# 24line-control-panel.net
KiCad netlist of a schematic drawn in Altium Designer
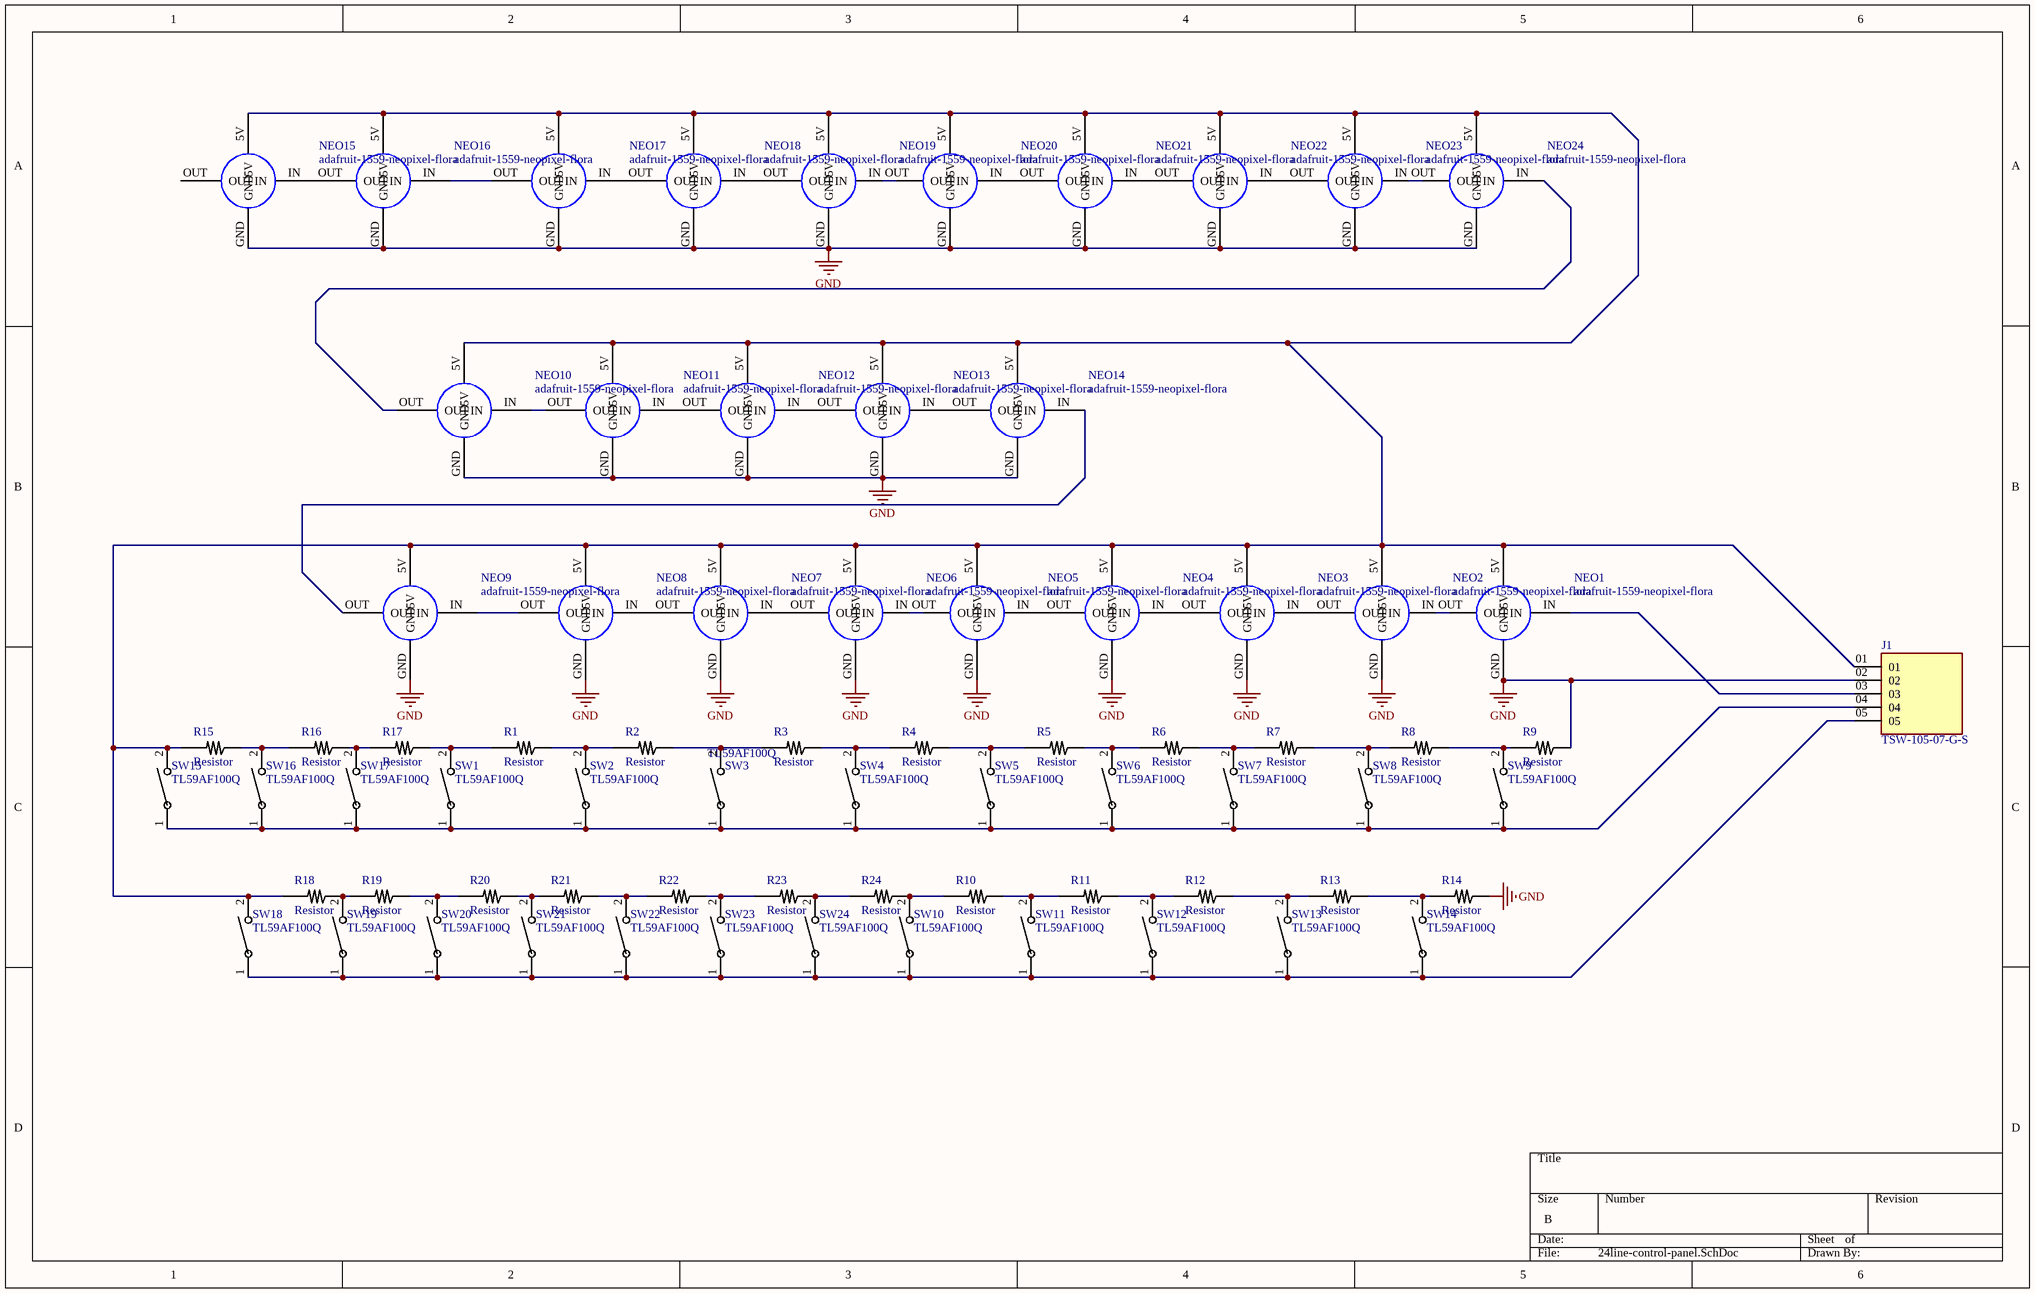
[diagram p0: 24line-control-panel.SchDoc]

(export (version "E")
  (design (tool "Eeschema 10.0.6"))
  (components
    (comp (ref "J1")
      (value "TSW-105-07-G-S")
      (footprint "SAMTEC_TSW-105-07-G-S")
      (fields (field (name "MF") "Samtec Inc."))
      (libsource (lib "SchlibLafe") (part "TSW-105-07-G-S"))
    )
    (comp (ref "NEO1")
      (value "adafruit-1559-neopixel-flora")
      (footprint "adafruit-1559-neopixel-flora")
      (libsource (lib "SchlibLafe") (part "adafruit-1559-neopixel-flora"))
    )
    (comp (ref "NEO2")
      (value "adafruit-1559-neopixel-flora")
      (footprint "adafruit-1559-neopixel-flora")
      (libsource (lib "SchlibLafe") (part "adafruit-1559-neopixel-flora"))
    )
    (comp (ref "NEO3")
      (value "adafruit-1559-neopixel-flora")
      (footprint "adafruit-1559-neopixel-flora")
      (libsource (lib "SchlibLafe") (part "adafruit-1559-neopixel-flora"))
    )
    (comp (ref "NEO4")
      (value "adafruit-1559-neopixel-flora")
      (footprint "adafruit-1559-neopixel-flora")
      (libsource (lib "SchlibLafe") (part "adafruit-1559-neopixel-flora"))
    )
    (comp (ref "NEO5")
      (value "adafruit-1559-neopixel-flora")
      (footprint "adafruit-1559-neopixel-flora")
      (libsource (lib "SchlibLafe") (part "adafruit-1559-neopixel-flora"))
    )
    (comp (ref "NEO6")
      (value "adafruit-1559-neopixel-flora")
      (footprint "adafruit-1559-neopixel-flora")
      (libsource (lib "SchlibLafe") (part "adafruit-1559-neopixel-flora"))
    )
    (comp (ref "NEO7")
      (value "adafruit-1559-neopixel-flora")
      (footprint "adafruit-1559-neopixel-flora")
      (libsource (lib "SchlibLafe") (part "adafruit-1559-neopixel-flora"))
    )
    (comp (ref "NEO8")
      (value "adafruit-1559-neopixel-flora")
      (footprint "adafruit-1559-neopixel-flora")
      (libsource (lib "SchlibLafe") (part "adafruit-1559-neopixel-flora"))
    )
    (comp (ref "NEO9")
      (value "adafruit-1559-neopixel-flora")
      (footprint "adafruit-1559-neopixel-flora")
      (libsource (lib "SchlibLafe") (part "adafruit-1559-neopixel-flora"))
    )
    (comp (ref "NEO10")
      (value "adafruit-1559-neopixel-flora")
      (footprint "adafruit-1559-neopixel-flora")
      (libsource (lib "SchlibLafe") (part "adafruit-1559-neopixel-flora"))
    )
    (comp (ref "NEO11")
      (value "adafruit-1559-neopixel-flora")
      (footprint "adafruit-1559-neopixel-flora")
      (libsource (lib "SchlibLafe") (part "adafruit-1559-neopixel-flora"))
    )
    (comp (ref "NEO12")
      (value "adafruit-1559-neopixel-flora")
      (footprint "adafruit-1559-neopixel-flora")
      (libsource (lib "SchlibLafe") (part "adafruit-1559-neopixel-flora"))
    )
    (comp (ref "NEO13")
      (value "adafruit-1559-neopixel-flora")
      (footprint "adafruit-1559-neopixel-flora")
      (libsource (lib "SchlibLafe") (part "adafruit-1559-neopixel-flora"))
    )
    (comp (ref "NEO14")
      (value "adafruit-1559-neopixel-flora")
      (footprint "adafruit-1559-neopixel-flora")
      (libsource (lib "SchlibLafe") (part "adafruit-1559-neopixel-flora"))
    )
    (comp (ref "NEO15")
      (value "adafruit-1559-neopixel-flora")
      (footprint "adafruit-1559-neopixel-flora")
      (libsource (lib "SchlibLafe") (part "adafruit-1559-neopixel-flora"))
    )
    (comp (ref "NEO16")
      (value "adafruit-1559-neopixel-flora")
      (footprint "adafruit-1559-neopixel-flora")
      (libsource (lib "SchlibLafe") (part "adafruit-1559-neopixel-flora"))
    )
    (comp (ref "NEO17")
      (value "adafruit-1559-neopixel-flora")
      (footprint "adafruit-1559-neopixel-flora")
      (libsource (lib "SchlibLafe") (part "adafruit-1559-neopixel-flora"))
    )
    (comp (ref "NEO18")
      (value "adafruit-1559-neopixel-flora")
      (footprint "adafruit-1559-neopixel-flora")
      (libsource (lib "SchlibLafe") (part "adafruit-1559-neopixel-flora"))
    )
    (comp (ref "NEO19")
      (value "adafruit-1559-neopixel-flora")
      (footprint "adafruit-1559-neopixel-flora")
      (libsource (lib "SchlibLafe") (part "adafruit-1559-neopixel-flora"))
    )
    (comp (ref "NEO20")
      (value "adafruit-1559-neopixel-flora")
      (footprint "adafruit-1559-neopixel-flora")
      (libsource (lib "SchlibLafe") (part "adafruit-1559-neopixel-flora"))
    )
    (comp (ref "NEO21")
      (value "adafruit-1559-neopixel-flora")
      (footprint "adafruit-1559-neopixel-flora")
      (libsource (lib "SchlibLafe") (part "adafruit-1559-neopixel-flora"))
    )
    (comp (ref "NEO22")
      (value "adafruit-1559-neopixel-flora")
      (footprint "adafruit-1559-neopixel-flora")
      (libsource (lib "SchlibLafe") (part "adafruit-1559-neopixel-flora"))
    )
    (comp (ref "NEO23")
      (value "adafruit-1559-neopixel-flora")
      (footprint "adafruit-1559-neopixel-flora")
      (libsource (lib "SchlibLafe") (part "adafruit-1559-neopixel-flora"))
    )
    (comp (ref "NEO24")
      (value "adafruit-1559-neopixel-flora")
      (footprint "adafruit-1559-neopixel-flora")
      (libsource (lib "SchlibLafe") (part "adafruit-1559-neopixel-flora"))
    )
    (comp (ref "R1")
      (value "Resistor")
      (footprint "thruhole resistor")
      (libsource (lib "SchlibLafe") (part "Resistor"))
    )
    (comp (ref "R2")
      (value "Resistor")
      (footprint "thruhole resistor")
      (libsource (lib "SchlibLafe") (part "Resistor"))
    )
    (comp (ref "R3")
      (value "Resistor")
      (footprint "thruhole resistor")
      (libsource (lib "SchlibLafe") (part "Resistor"))
    )
    (comp (ref "R4")
      (value "Resistor")
      (footprint "thruhole resistor")
      (libsource (lib "SchlibLafe") (part "Resistor"))
    )
    (comp (ref "R5")
      (value "Resistor")
      (footprint "thruhole resistor")
      (libsource (lib "SchlibLafe") (part "Resistor"))
    )
    (comp (ref "R6")
      (value "Resistor")
      (footprint "thruhole resistor")
      (libsource (lib "SchlibLafe") (part "Resistor"))
    )
    (comp (ref "R7")
      (value "Resistor")
      (footprint "thruhole resistor")
      (libsource (lib "SchlibLafe") (part "Resistor"))
    )
    (comp (ref "R8")
      (value "Resistor")
      (footprint "thruhole resistor")
      (libsource (lib "SchlibLafe") (part "Resistor"))
    )
    (comp (ref "R9")
      (value "Resistor")
      (footprint "thruhole resistor")
      (libsource (lib "SchlibLafe") (part "Resistor"))
    )
    (comp (ref "R10")
      (value "Resistor")
      (footprint "thruhole resistor")
      (libsource (lib "SchlibLafe") (part "Resistor"))
    )
    (comp (ref "R11")
      (value "Resistor")
      (footprint "thruhole resistor")
      (libsource (lib "SchlibLafe") (part "Resistor"))
    )
    (comp (ref "R12")
      (value "Resistor")
      (footprint "thruhole resistor")
      (libsource (lib "SchlibLafe") (part "Resistor"))
    )
    (comp (ref "R13")
      (value "Resistor")
      (footprint "thruhole resistor")
      (libsource (lib "SchlibLafe") (part "Resistor"))
    )
    (comp (ref "R14")
      (value "Resistor")
      (footprint "thruhole resistor")
      (libsource (lib "SchlibLafe") (part "Resistor"))
    )
    (comp (ref "R15")
      (value "Resistor")
      (footprint "thruhole resistor")
      (libsource (lib "SchlibLafe") (part "Resistor"))
    )
    (comp (ref "R16")
      (value "Resistor")
      (footprint "thruhole resistor")
      (libsource (lib "SchlibLafe") (part "Resistor"))
    )
    (comp (ref "R17")
      (value "Resistor")
      (footprint "thruhole resistor")
      (libsource (lib "SchlibLafe") (part "Resistor"))
    )
    (comp (ref "R18")
      (value "Resistor")
      (footprint "thruhole resistor")
      (libsource (lib "SchlibLafe") (part "Resistor"))
    )
    (comp (ref "R19")
      (value "Resistor")
      (footprint "thruhole resistor")
      (libsource (lib "SchlibLafe") (part "Resistor"))
    )
    (comp (ref "R20")
      (value "Resistor")
      (footprint "thruhole resistor")
      (libsource (lib "SchlibLafe") (part "Resistor"))
    )
    (comp (ref "R21")
      (value "Resistor")
      (footprint "thruhole resistor")
      (libsource (lib "SchlibLafe") (part "Resistor"))
    )
    (comp (ref "R22")
      (value "Resistor")
      (footprint "thruhole resistor")
      (libsource (lib "SchlibLafe") (part "Resistor"))
    )
    (comp (ref "R23")
      (value "Resistor")
      (footprint "thruhole resistor")
      (libsource (lib "SchlibLafe") (part "Resistor"))
    )
    (comp (ref "R24")
      (value "Resistor")
      (footprint "thruhole resistor")
      (libsource (lib "SchlibLafe") (part "Resistor"))
    )
    (comp (ref "SW1")
      (value "TL59AF100Q")
      (footprint "SW_TL59AF100Q_EWI")
      (description "No Description Available")
      (fields (field (name "COPYRIGHT") "Copyright (C) 2024 Ultra Librarian. All rights reserved."))
      (libsource (lib "SchlibLafe") (part "TL59AF100Q"))
    )
    (comp (ref "SW2")
      (value "TL59AF100Q")
      (footprint "SW_TL59AF100Q_EWI")
      (description "No Description Available")
      (fields (field (name "COPYRIGHT") "Copyright (C) 2024 Ultra Librarian. All rights reserved."))
      (libsource (lib "SchlibLafe") (part "TL59AF100Q"))
    )
    (comp (ref "SW3")
      (value "TL59AF100Q")
      (footprint "SW_TL59AF100Q_EWI")
      (description "No Description Available")
      (fields (field (name "COPYRIGHT") "Copyright (C) 2024 Ultra Librarian. All rights reserved."))
      (libsource (lib "SchlibLafe") (part "TL59AF100Q"))
    )
    (comp (ref "SW4")
      (value "TL59AF100Q")
      (footprint "SW_TL59AF100Q_EWI")
      (description "No Description Available")
      (fields (field (name "COPYRIGHT") "Copyright (C) 2024 Ultra Librarian. All rights reserved."))
      (libsource (lib "SchlibLafe") (part "TL59AF100Q"))
    )
    (comp (ref "SW5")
      (value "TL59AF100Q")
      (footprint "SW_TL59AF100Q_EWI")
      (description "No Description Available")
      (fields (field (name "COPYRIGHT") "Copyright (C) 2024 Ultra Librarian. All rights reserved."))
      (libsource (lib "SchlibLafe") (part "TL59AF100Q"))
    )
    (comp (ref "SW6")
      (value "TL59AF100Q")
      (footprint "SW_TL59AF100Q_EWI")
      (description "No Description Available")
      (fields (field (name "COPYRIGHT") "Copyright (C) 2024 Ultra Librarian. All rights reserved."))
      (libsource (lib "SchlibLafe") (part "TL59AF100Q"))
    )
    (comp (ref "SW7")
      (value "TL59AF100Q")
      (footprint "SW_TL59AF100Q_EWI")
      (description "No Description Available")
      (fields (field (name "COPYRIGHT") "Copyright (C) 2024 Ultra Librarian. All rights reserved."))
      (libsource (lib "SchlibLafe") (part "TL59AF100Q"))
    )
    (comp (ref "SW8")
      (value "TL59AF100Q")
      (footprint "SW_TL59AF100Q_EWI")
      (description "No Description Available")
      (fields (field (name "COPYRIGHT") "Copyright (C) 2024 Ultra Librarian. All rights reserved."))
      (libsource (lib "SchlibLafe") (part "TL59AF100Q"))
    )
    (comp (ref "SW9")
      (value "TL59AF100Q")
      (footprint "SW_TL59AF100Q_EWI")
      (description "No Description Available")
      (fields (field (name "COPYRIGHT") "Copyright (C) 2024 Ultra Librarian. All rights reserved."))
      (libsource (lib "SchlibLafe") (part "TL59AF100Q"))
    )
    (comp (ref "SW10")
      (value "TL59AF100Q")
      (footprint "SW_TL59AF100Q_EWI")
      (description "No Description Available")
      (fields (field (name "COPYRIGHT") "Copyright (C) 2024 Ultra Librarian. All rights reserved."))
      (libsource (lib "SchlibLafe") (part "TL59AF100Q"))
    )
    (comp (ref "SW11")
      (value "TL59AF100Q")
      (footprint "SW_TL59AF100Q_EWI")
      (description "No Description Available")
      (fields (field (name "COPYRIGHT") "Copyright (C) 2024 Ultra Librarian. All rights reserved."))
      (libsource (lib "SchlibLafe") (part "TL59AF100Q"))
    )
    (comp (ref "SW12")
      (value "TL59AF100Q")
      (footprint "SW_TL59AF100Q_EWI")
      (description "No Description Available")
      (fields (field (name "COPYRIGHT") "Copyright (C) 2024 Ultra Librarian. All rights reserved."))
      (libsource (lib "SchlibLafe") (part "TL59AF100Q"))
    )
    (comp (ref "SW13")
      (value "TL59AF100Q")
      (footprint "SW_TL59AF100Q_EWI")
      (description "No Description Available")
      (fields (field (name "COPYRIGHT") "Copyright (C) 2024 Ultra Librarian. All rights reserved."))
      (libsource (lib "SchlibLafe") (part "TL59AF100Q"))
    )
    (comp (ref "SW14")
      (value "TL59AF100Q")
      (footprint "SW_TL59AF100Q_EWI")
      (description "No Description Available")
      (fields (field (name "COPYRIGHT") "Copyright (C) 2024 Ultra Librarian. All rights reserved."))
      (libsource (lib "SchlibLafe") (part "TL59AF100Q"))
    )
    (comp (ref "SW15")
      (value "TL59AF100Q")
      (footprint "SW_TL59AF100Q_EWI")
      (description "No Description Available")
      (fields (field (name "COPYRIGHT") "Copyright (C) 2024 Ultra Librarian. All rights reserved."))
      (libsource (lib "SchlibLafe") (part "TL59AF100Q"))
    )
    (comp (ref "SW16")
      (value "TL59AF100Q")
      (footprint "SW_TL59AF100Q_EWI")
      (description "No Description Available")
      (fields (field (name "COPYRIGHT") "Copyright (C) 2024 Ultra Librarian. All rights reserved."))
      (libsource (lib "SchlibLafe") (part "TL59AF100Q"))
    )
    (comp (ref "SW17")
      (value "TL59AF100Q")
      (footprint "SW_TL59AF100Q_EWI")
      (description "No Description Available")
      (fields (field (name "COPYRIGHT") "Copyright (C) 2024 Ultra Librarian. All rights reserved."))
      (libsource (lib "SchlibLafe") (part "TL59AF100Q"))
    )
    (comp (ref "SW18")
      (value "TL59AF100Q")
      (footprint "SW_TL59AF100Q_EWI")
      (description "No Description Available")
      (fields (field (name "COPYRIGHT") "Copyright (C) 2024 Ultra Librarian. All rights reserved."))
      (libsource (lib "SchlibLafe") (part "TL59AF100Q"))
    )
    (comp (ref "SW19")
      (value "TL59AF100Q")
      (footprint "SW_TL59AF100Q_EWI")
      (description "No Description Available")
      (fields (field (name "COPYRIGHT") "Copyright (C) 2024 Ultra Librarian. All rights reserved."))
      (libsource (lib "SchlibLafe") (part "TL59AF100Q"))
    )
    (comp (ref "SW20")
      (value "TL59AF100Q")
      (footprint "SW_TL59AF100Q_EWI")
      (description "No Description Available")
      (fields (field (name "COPYRIGHT") "Copyright (C) 2024 Ultra Librarian. All rights reserved."))
      (libsource (lib "SchlibLafe") (part "TL59AF100Q"))
    )
    (comp (ref "SW21")
      (value "TL59AF100Q")
      (footprint "SW_TL59AF100Q_EWI")
      (description "No Description Available")
      (fields (field (name "COPYRIGHT") "Copyright (C) 2024 Ultra Librarian. All rights reserved."))
      (libsource (lib "SchlibLafe") (part "TL59AF100Q"))
    )
    (comp (ref "SW22")
      (value "TL59AF100Q")
      (footprint "SW_TL59AF100Q_EWI")
      (description "No Description Available")
      (fields (field (name "COPYRIGHT") "Copyright (C) 2024 Ultra Librarian. All rights reserved."))
      (libsource (lib "SchlibLafe") (part "TL59AF100Q"))
    )
    (comp (ref "SW23")
      (value "TL59AF100Q")
      (footprint "SW_TL59AF100Q_EWI")
      (description "No Description Available")
      (fields (field (name "COPYRIGHT") "Copyright (C) 2024 Ultra Librarian. All rights reserved."))
      (libsource (lib "SchlibLafe") (part "TL59AF100Q"))
    )
    (comp (ref "SW24")
      (value "TL59AF100Q")
      (footprint "SW_TL59AF100Q_EWI")
      (description "No Description Available")
      (fields (field (name "COPYRIGHT") "Copyright (C) 2024 Ultra Librarian. All rights reserved."))
      (libsource (lib "SchlibLafe") (part "TL59AF100Q"))
    )
  )
  (nets
    (net (code "1") (name "GND") (class "Default")
      (node (ref "J1") (pin "02") (pinfunction "02_02") (pintype "passive"))
      (node (ref "NEO1") (pin "GND") (pinfunction "GND_GND") (pintype "passive"))
      (node (ref "NEO10") (pin "GND") (pinfunction "GND_GND") (pintype "passive"))
      (node (ref "NEO11") (pin "GND") (pinfunction "GND_GND") (pintype "passive"))
      (node (ref "NEO12") (pin "GND") (pinfunction "GND_GND") (pintype "passive"))
      (node (ref "NEO13") (pin "GND") (pinfunction "GND_GND") (pintype "passive"))
      (node (ref "NEO14") (pin "GND") (pinfunction "GND_GND") (pintype "passive"))
      (node (ref "NEO15") (pin "GND") (pinfunction "GND_GND") (pintype "passive"))
      (node (ref "NEO16") (pin "GND") (pinfunction "GND_GND") (pintype "passive"))
      (node (ref "NEO17") (pin "GND") (pinfunction "GND_GND") (pintype "passive"))
      (node (ref "NEO18") (pin "GND") (pinfunction "GND_GND") (pintype "passive"))
      (node (ref "NEO19") (pin "GND") (pinfunction "GND_GND") (pintype "passive"))
      (node (ref "NEO2") (pin "GND") (pinfunction "GND_GND") (pintype "passive"))
      (node (ref "NEO20") (pin "GND") (pinfunction "GND_GND") (pintype "passive"))
      (node (ref "NEO21") (pin "GND") (pinfunction "GND_GND") (pintype "passive"))
      (node (ref "NEO22") (pin "GND") (pinfunction "GND_GND") (pintype "passive"))
      (node (ref "NEO23") (pin "GND") (pinfunction "GND_GND") (pintype "passive"))
      (node (ref "NEO24") (pin "GND") (pinfunction "GND_GND") (pintype "passive"))
      (node (ref "NEO3") (pin "GND") (pinfunction "GND_GND") (pintype "passive"))
      (node (ref "NEO4") (pin "GND") (pinfunction "GND_GND") (pintype "passive"))
      (node (ref "NEO5") (pin "GND") (pinfunction "GND_GND") (pintype "passive"))
      (node (ref "NEO6") (pin "GND") (pinfunction "GND_GND") (pintype "passive"))
      (node (ref "NEO7") (pin "GND") (pinfunction "GND_GND") (pintype "passive"))
      (node (ref "NEO8") (pin "GND") (pinfunction "GND_GND") (pintype "passive"))
      (node (ref "NEO9") (pin "GND") (pinfunction "GND_GND") (pintype "passive"))
      (node (ref "R14") (pin "1") (pinfunction "1_1") (pintype "passive"))
      (node (ref "R9") (pin "1") (pinfunction "1_1") (pintype "passive"))
    )
    (net (code "2") (name "Net-(J1-Pad01)") (class "Default")
      (node (ref "J1") (pin "01") (pinfunction "01_01") (pintype "passive"))
      (node (ref "NEO1") (pin "5V") (pinfunction "5V_5V") (pintype "passive"))
      (node (ref "NEO10") (pin "5V") (pinfunction "5V_5V") (pintype "passive"))
      (node (ref "NEO11") (pin "5V") (pinfunction "5V_5V") (pintype "passive"))
      (node (ref "NEO12") (pin "5V") (pinfunction "5V_5V") (pintype "passive"))
      (node (ref "NEO13") (pin "5V") (pinfunction "5V_5V") (pintype "passive"))
      (node (ref "NEO14") (pin "5V") (pinfunction "5V_5V") (pintype "passive"))
      (node (ref "NEO15") (pin "5V") (pinfunction "5V_5V") (pintype "passive"))
      (node (ref "NEO16") (pin "5V") (pinfunction "5V_5V") (pintype "passive"))
      (node (ref "NEO17") (pin "5V") (pinfunction "5V_5V") (pintype "passive"))
      (node (ref "NEO18") (pin "5V") (pinfunction "5V_5V") (pintype "passive"))
      (node (ref "NEO19") (pin "5V") (pinfunction "5V_5V") (pintype "passive"))
      (node (ref "NEO2") (pin "5V") (pinfunction "5V_5V") (pintype "passive"))
      (node (ref "NEO20") (pin "5V") (pinfunction "5V_5V") (pintype "passive"))
      (node (ref "NEO21") (pin "5V") (pinfunction "5V_5V") (pintype "passive"))
      (node (ref "NEO22") (pin "5V") (pinfunction "5V_5V") (pintype "passive"))
      (node (ref "NEO23") (pin "5V") (pinfunction "5V_5V") (pintype "passive"))
      (node (ref "NEO24") (pin "5V") (pinfunction "5V_5V") (pintype "passive"))
      (node (ref "NEO3") (pin "5V") (pinfunction "5V_5V") (pintype "passive"))
      (node (ref "NEO4") (pin "5V") (pinfunction "5V_5V") (pintype "passive"))
      (node (ref "NEO5") (pin "5V") (pinfunction "5V_5V") (pintype "passive"))
      (node (ref "NEO6") (pin "5V") (pinfunction "5V_5V") (pintype "passive"))
      (node (ref "NEO7") (pin "5V") (pinfunction "5V_5V") (pintype "passive"))
      (node (ref "NEO8") (pin "5V") (pinfunction "5V_5V") (pintype "passive"))
      (node (ref "NEO9") (pin "5V") (pinfunction "5V_5V") (pintype "passive"))
      (node (ref "R15") (pin "2") (pinfunction "2_2") (pintype "passive"))
      (node (ref "R18") (pin "2") (pinfunction "2_2") (pintype "passive"))
      (node (ref "SW15") (pin "2") (pinfunction "2_2") (pintype "passive"))
      (node (ref "SW18") (pin "2") (pinfunction "2_2") (pintype "passive"))
    )
    (net (code "3") (name "Net-(J1-Pad03)") (class "Default")
      (node (ref "J1") (pin "03") (pinfunction "03_03") (pintype "passive"))
      (node (ref "NEO1") (pin "IN") (pinfunction "IN_IN") (pintype "passive"))
    )
    (net (code "4") (name "Net-(J1-Pad04)") (class "Default")
      (node (ref "J1") (pin "04") (pinfunction "04_04") (pintype "passive"))
      (node (ref "SW1") (pin "1") (pinfunction "1_1") (pintype "passive"))
      (node (ref "SW15") (pin "1") (pinfunction "1_1") (pintype "passive"))
      (node (ref "SW16") (pin "1") (pinfunction "1_1") (pintype "passive"))
      (node (ref "SW17") (pin "1") (pinfunction "1_1") (pintype "passive"))
      (node (ref "SW2") (pin "1") (pinfunction "1_1") (pintype "passive"))
      (node (ref "SW3") (pin "1") (pinfunction "1_1") (pintype "passive"))
      (node (ref "SW4") (pin "1") (pinfunction "1_1") (pintype "passive"))
      (node (ref "SW5") (pin "1") (pinfunction "1_1") (pintype "passive"))
      (node (ref "SW6") (pin "1") (pinfunction "1_1") (pintype "passive"))
      (node (ref "SW7") (pin "1") (pinfunction "1_1") (pintype "passive"))
      (node (ref "SW8") (pin "1") (pinfunction "1_1") (pintype "passive"))
      (node (ref "SW9") (pin "1") (pinfunction "1_1") (pintype "passive"))
    )
    (net (code "5") (name "Net-(J1-Pad05)") (class "Default")
      (node (ref "J1") (pin "05") (pinfunction "05_05") (pintype "passive"))
      (node (ref "SW10") (pin "1") (pinfunction "1_1") (pintype "passive"))
      (node (ref "SW11") (pin "1") (pinfunction "1_1") (pintype "passive"))
      (node (ref "SW12") (pin "1") (pinfunction "1_1") (pintype "passive"))
      (node (ref "SW13") (pin "1") (pinfunction "1_1") (pintype "passive"))
      (node (ref "SW14") (pin "1") (pinfunction "1_1") (pintype "passive"))
      (node (ref "SW18") (pin "1") (pinfunction "1_1") (pintype "passive"))
      (node (ref "SW19") (pin "1") (pinfunction "1_1") (pintype "passive"))
      (node (ref "SW20") (pin "1") (pinfunction "1_1") (pintype "passive"))
      (node (ref "SW21") (pin "1") (pinfunction "1_1") (pintype "passive"))
      (node (ref "SW22") (pin "1") (pinfunction "1_1") (pintype "passive"))
      (node (ref "SW23") (pin "1") (pinfunction "1_1") (pintype "passive"))
      (node (ref "SW24") (pin "1") (pinfunction "1_1") (pintype "passive"))
    )
    (net (code "6") (name "Net-(NEO1-PadOUT)") (class "Default")
      (node (ref "NEO1") (pin "OUT") (pinfunction "OUT_OUT") (pintype "passive"))
      (node (ref "NEO2") (pin "IN") (pinfunction "IN_IN") (pintype "passive"))
    )
    (net (code "7") (name "Net-(NEO2-PadOUT)") (class "Default")
      (node (ref "NEO2") (pin "OUT") (pinfunction "OUT_OUT") (pintype "passive"))
      (node (ref "NEO3") (pin "IN") (pinfunction "IN_IN") (pintype "passive"))
    )
    (net (code "8") (name "Net-(NEO3-PadOUT)") (class "Default")
      (node (ref "NEO3") (pin "OUT") (pinfunction "OUT_OUT") (pintype "passive"))
      (node (ref "NEO4") (pin "IN") (pinfunction "IN_IN") (pintype "passive"))
    )
    (net (code "9") (name "Net-(NEO4-PadOUT)") (class "Default")
      (node (ref "NEO4") (pin "OUT") (pinfunction "OUT_OUT") (pintype "passive"))
      (node (ref "NEO5") (pin "IN") (pinfunction "IN_IN") (pintype "passive"))
    )
    (net (code "10") (name "Net-(NEO5-PadOUT)") (class "Default")
      (node (ref "NEO5") (pin "OUT") (pinfunction "OUT_OUT") (pintype "passive"))
      (node (ref "NEO6") (pin "IN") (pinfunction "IN_IN") (pintype "passive"))
    )
    (net (code "11") (name "Net-(NEO6-PadOUT)") (class "Default")
      (node (ref "NEO6") (pin "OUT") (pinfunction "OUT_OUT") (pintype "passive"))
      (node (ref "NEO7") (pin "IN") (pinfunction "IN_IN") (pintype "passive"))
    )
    (net (code "12") (name "Net-(NEO7-PadOUT)") (class "Default")
      (node (ref "NEO7") (pin "OUT") (pinfunction "OUT_OUT") (pintype "passive"))
      (node (ref "NEO8") (pin "IN") (pinfunction "IN_IN") (pintype "passive"))
    )
    (net (code "13") (name "Net-(NEO8-PadOUT)") (class "Default")
      (node (ref "NEO8") (pin "OUT") (pinfunction "OUT_OUT") (pintype "passive"))
      (node (ref "NEO9") (pin "IN") (pinfunction "IN_IN") (pintype "passive"))
    )
    (net (code "14") (name "Net-(NEO10-PadIN)") (class "Default")
      (node (ref "NEO10") (pin "IN") (pinfunction "IN_IN") (pintype "passive"))
      (node (ref "NEO11") (pin "OUT") (pinfunction "OUT_OUT") (pintype "passive"))
    )
    (net (code "15") (name "Net-(NEO10-PadOUT)") (class "Default")
      (node (ref "NEO10") (pin "OUT") (pinfunction "OUT_OUT") (pintype "passive"))
      (node (ref "NEO24") (pin "IN") (pinfunction "IN_IN") (pintype "passive"))
    )
    (net (code "16") (name "Net-(NEO11-PadIN)") (class "Default")
      (node (ref "NEO11") (pin "IN") (pinfunction "IN_IN") (pintype "passive"))
      (node (ref "NEO12") (pin "OUT") (pinfunction "OUT_OUT") (pintype "passive"))
    )
    (net (code "17") (name "Net-(NEO12-PadIN)") (class "Default")
      (node (ref "NEO12") (pin "IN") (pinfunction "IN_IN") (pintype "passive"))
      (node (ref "NEO13") (pin "OUT") (pinfunction "OUT_OUT") (pintype "passive"))
    )
    (net (code "18") (name "Net-(NEO13-PadIN)") (class "Default")
      (node (ref "NEO13") (pin "IN") (pinfunction "IN_IN") (pintype "passive"))
      (node (ref "NEO14") (pin "OUT") (pinfunction "OUT_OUT") (pintype "passive"))
    )
    (net (code "19") (name "Net-(NEO14-PadIN)") (class "Default")
      (node (ref "NEO14") (pin "IN") (pinfunction "IN_IN") (pintype "passive"))
      (node (ref "NEO9") (pin "OUT") (pinfunction "OUT_OUT") (pintype "passive"))
    )
    (net (code "20") (name "Net-(NEO15-PadIN)") (class "Default")
      (node (ref "NEO15") (pin "IN") (pinfunction "IN_IN") (pintype "passive"))
      (node (ref "NEO16") (pin "OUT") (pinfunction "OUT_OUT") (pintype "passive"))
    )
    (net (code "21") (name "Net-(NEO16-PadIN)") (class "Default")
      (node (ref "NEO16") (pin "IN") (pinfunction "IN_IN") (pintype "passive"))
      (node (ref "NEO17") (pin "OUT") (pinfunction "OUT_OUT") (pintype "passive"))
    )
    (net (code "22") (name "Net-(NEO17-PadIN)") (class "Default")
      (node (ref "NEO17") (pin "IN") (pinfunction "IN_IN") (pintype "passive"))
      (node (ref "NEO18") (pin "OUT") (pinfunction "OUT_OUT") (pintype "passive"))
    )
    (net (code "23") (name "Net-(NEO18-PadIN)") (class "Default")
      (node (ref "NEO18") (pin "IN") (pinfunction "IN_IN") (pintype "passive"))
      (node (ref "NEO19") (pin "OUT") (pinfunction "OUT_OUT") (pintype "passive"))
    )
    (net (code "24") (name "Net-(NEO19-PadIN)") (class "Default")
      (node (ref "NEO19") (pin "IN") (pinfunction "IN_IN") (pintype "passive"))
      (node (ref "NEO20") (pin "OUT") (pinfunction "OUT_OUT") (pintype "passive"))
    )
    (net (code "25") (name "Net-(NEO20-PadIN)") (class "Default")
      (node (ref "NEO20") (pin "IN") (pinfunction "IN_IN") (pintype "passive"))
      (node (ref "NEO21") (pin "OUT") (pinfunction "OUT_OUT") (pintype "passive"))
    )
    (net (code "26") (name "Net-(NEO21-PadIN)") (class "Default")
      (node (ref "NEO21") (pin "IN") (pinfunction "IN_IN") (pintype "passive"))
      (node (ref "NEO22") (pin "OUT") (pinfunction "OUT_OUT") (pintype "passive"))
    )
    (net (code "27") (name "Net-(NEO22-PadIN)") (class "Default")
      (node (ref "NEO22") (pin "IN") (pinfunction "IN_IN") (pintype "passive"))
      (node (ref "NEO23") (pin "OUT") (pinfunction "OUT_OUT") (pintype "passive"))
    )
    (net (code "28") (name "Net-(NEO23-PadIN)") (class "Default")
      (node (ref "NEO23") (pin "IN") (pinfunction "IN_IN") (pintype "passive"))
      (node (ref "NEO24") (pin "OUT") (pinfunction "OUT_OUT") (pintype "passive"))
    )
    (net (code "29") (name "Net-(R1-Pad1)") (class "Default")
      (node (ref "R1") (pin "1") (pinfunction "1_1") (pintype "passive"))
      (node (ref "R2") (pin "2") (pinfunction "2_2") (pintype "passive"))
      (node (ref "SW2") (pin "2") (pinfunction "2_2") (pintype "passive"))
    )
    (net (code "30") (name "Net-(R1-Pad2)") (class "Default")
      (node (ref "R1") (pin "2") (pinfunction "2_2") (pintype "passive"))
      (node (ref "R17") (pin "1") (pinfunction "1_1") (pintype "passive"))
      (node (ref "SW1") (pin "2") (pinfunction "2_2") (pintype "passive"))
    )
    (net (code "31") (name "Net-(R2-Pad1)") (class "Default")
      (node (ref "R2") (pin "1") (pinfunction "1_1") (pintype "passive"))
      (node (ref "R3") (pin "2") (pinfunction "2_2") (pintype "passive"))
      (node (ref "SW3") (pin "2") (pinfunction "2_2") (pintype "passive"))
    )
    (net (code "32") (name "Net-(R3-Pad1)") (class "Default")
      (node (ref "R3") (pin "1") (pinfunction "1_1") (pintype "passive"))
      (node (ref "R4") (pin "2") (pinfunction "2_2") (pintype "passive"))
      (node (ref "SW4") (pin "2") (pinfunction "2_2") (pintype "passive"))
    )
    (net (code "33") (name "Net-(R4-Pad1)") (class "Default")
      (node (ref "R4") (pin "1") (pinfunction "1_1") (pintype "passive"))
      (node (ref "R5") (pin "2") (pinfunction "2_2") (pintype "passive"))
      (node (ref "SW5") (pin "2") (pinfunction "2_2") (pintype "passive"))
    )
    (net (code "34") (name "Net-(R5-Pad1)") (class "Default")
      (node (ref "R5") (pin "1") (pinfunction "1_1") (pintype "passive"))
      (node (ref "R6") (pin "2") (pinfunction "2_2") (pintype "passive"))
      (node (ref "SW6") (pin "2") (pinfunction "2_2") (pintype "passive"))
    )
    (net (code "35") (name "Net-(R6-Pad1)") (class "Default")
      (node (ref "R6") (pin "1") (pinfunction "1_1") (pintype "passive"))
      (node (ref "R7") (pin "2") (pinfunction "2_2") (pintype "passive"))
      (node (ref "SW7") (pin "2") (pinfunction "2_2") (pintype "passive"))
    )
    (net (code "36") (name "Net-(R7-Pad1)") (class "Default")
      (node (ref "R7") (pin "1") (pinfunction "1_1") (pintype "passive"))
      (node (ref "R8") (pin "2") (pinfunction "2_2") (pintype "passive"))
      (node (ref "SW8") (pin "2") (pinfunction "2_2") (pintype "passive"))
    )
    (net (code "37") (name "Net-(R8-Pad1)") (class "Default")
      (node (ref "R8") (pin "1") (pinfunction "1_1") (pintype "passive"))
      (node (ref "R9") (pin "2") (pinfunction "2_2") (pintype "passive"))
      (node (ref "SW9") (pin "2") (pinfunction "2_2") (pintype "passive"))
    )
    (net (code "38") (name "Net-(R10-Pad1)") (class "Default")
      (node (ref "R10") (pin "1") (pinfunction "1_1") (pintype "passive"))
      (node (ref "R11") (pin "2") (pinfunction "2_2") (pintype "passive"))
      (node (ref "SW11") (pin "2") (pinfunction "2_2") (pintype "passive"))
    )
    (net (code "39") (name "Net-(R10-Pad2)") (class "Default")
      (node (ref "R10") (pin "2") (pinfunction "2_2") (pintype "passive"))
      (node (ref "R24") (pin "1") (pinfunction "1_1") (pintype "passive"))
      (node (ref "SW10") (pin "2") (pinfunction "2_2") (pintype "passive"))
    )
    (net (code "40") (name "Net-(R11-Pad1)") (class "Default")
      (node (ref "R11") (pin "1") (pinfunction "1_1") (pintype "passive"))
      (node (ref "R12") (pin "2") (pinfunction "2_2") (pintype "passive"))
      (node (ref "SW12") (pin "2") (pinfunction "2_2") (pintype "passive"))
    )
    (net (code "41") (name "Net-(R12-Pad1)") (class "Default")
      (node (ref "R12") (pin "1") (pinfunction "1_1") (pintype "passive"))
      (node (ref "R13") (pin "2") (pinfunction "2_2") (pintype "passive"))
      (node (ref "SW13") (pin "2") (pinfunction "2_2") (pintype "passive"))
    )
    (net (code "42") (name "Net-(R13-Pad1)") (class "Default")
      (node (ref "R13") (pin "1") (pinfunction "1_1") (pintype "passive"))
      (node (ref "R14") (pin "2") (pinfunction "2_2") (pintype "passive"))
      (node (ref "SW14") (pin "2") (pinfunction "2_2") (pintype "passive"))
    )
    (net (code "43") (name "Net-(R15-Pad1)") (class "Default")
      (node (ref "R15") (pin "1") (pinfunction "1_1") (pintype "passive"))
      (node (ref "R16") (pin "2") (pinfunction "2_2") (pintype "passive"))
      (node (ref "SW16") (pin "2") (pinfunction "2_2") (pintype "passive"))
    )
    (net (code "44") (name "Net-(R16-Pad1)") (class "Default")
      (node (ref "R16") (pin "1") (pinfunction "1_1") (pintype "passive"))
      (node (ref "R17") (pin "2") (pinfunction "2_2") (pintype "passive"))
      (node (ref "SW17") (pin "2") (pinfunction "2_2") (pintype "passive"))
    )
    (net (code "45") (name "Net-(R18-Pad1)") (class "Default")
      (node (ref "R18") (pin "1") (pinfunction "1_1") (pintype "passive"))
      (node (ref "R19") (pin "2") (pinfunction "2_2") (pintype "passive"))
      (node (ref "SW19") (pin "2") (pinfunction "2_2") (pintype "passive"))
    )
    (net (code "46") (name "Net-(R19-Pad1)") (class "Default")
      (node (ref "R19") (pin "1") (pinfunction "1_1") (pintype "passive"))
      (node (ref "R20") (pin "2") (pinfunction "2_2") (pintype "passive"))
      (node (ref "SW20") (pin "2") (pinfunction "2_2") (pintype "passive"))
    )
    (net (code "47") (name "Net-(R20-Pad1)") (class "Default")
      (node (ref "R20") (pin "1") (pinfunction "1_1") (pintype "passive"))
      (node (ref "R21") (pin "2") (pinfunction "2_2") (pintype "passive"))
      (node (ref "SW21") (pin "2") (pinfunction "2_2") (pintype "passive"))
    )
    (net (code "48") (name "Net-(R21-Pad1)") (class "Default")
      (node (ref "R21") (pin "1") (pinfunction "1_1") (pintype "passive"))
      (node (ref "R22") (pin "2") (pinfunction "2_2") (pintype "passive"))
      (node (ref "SW22") (pin "2") (pinfunction "2_2") (pintype "passive"))
    )
    (net (code "49") (name "Net-(R22-Pad1)") (class "Default")
      (node (ref "R22") (pin "1") (pinfunction "1_1") (pintype "passive"))
      (node (ref "R23") (pin "2") (pinfunction "2_2") (pintype "passive"))
      (node (ref "SW23") (pin "2") (pinfunction "2_2") (pintype "passive"))
    )
    (net (code "50") (name "Net-(R23-Pad1)") (class "Default")
      (node (ref "R23") (pin "1") (pinfunction "1_1") (pintype "passive"))
      (node (ref "R24") (pin "2") (pinfunction "2_2") (pintype "passive"))
      (node (ref "SW24") (pin "2") (pinfunction "2_2") (pintype "passive"))
    )
    (net (code "51") (name "unconnected-(NEO15-PadOUT)") (class "Default")
      (node (ref "NEO15") (pin "OUT") (pinfunction "OUT_OUT") (pintype "passive"))
    )
  )
)
